# untitled.net
KiCad netlist of a schematic drawn in EAGLE
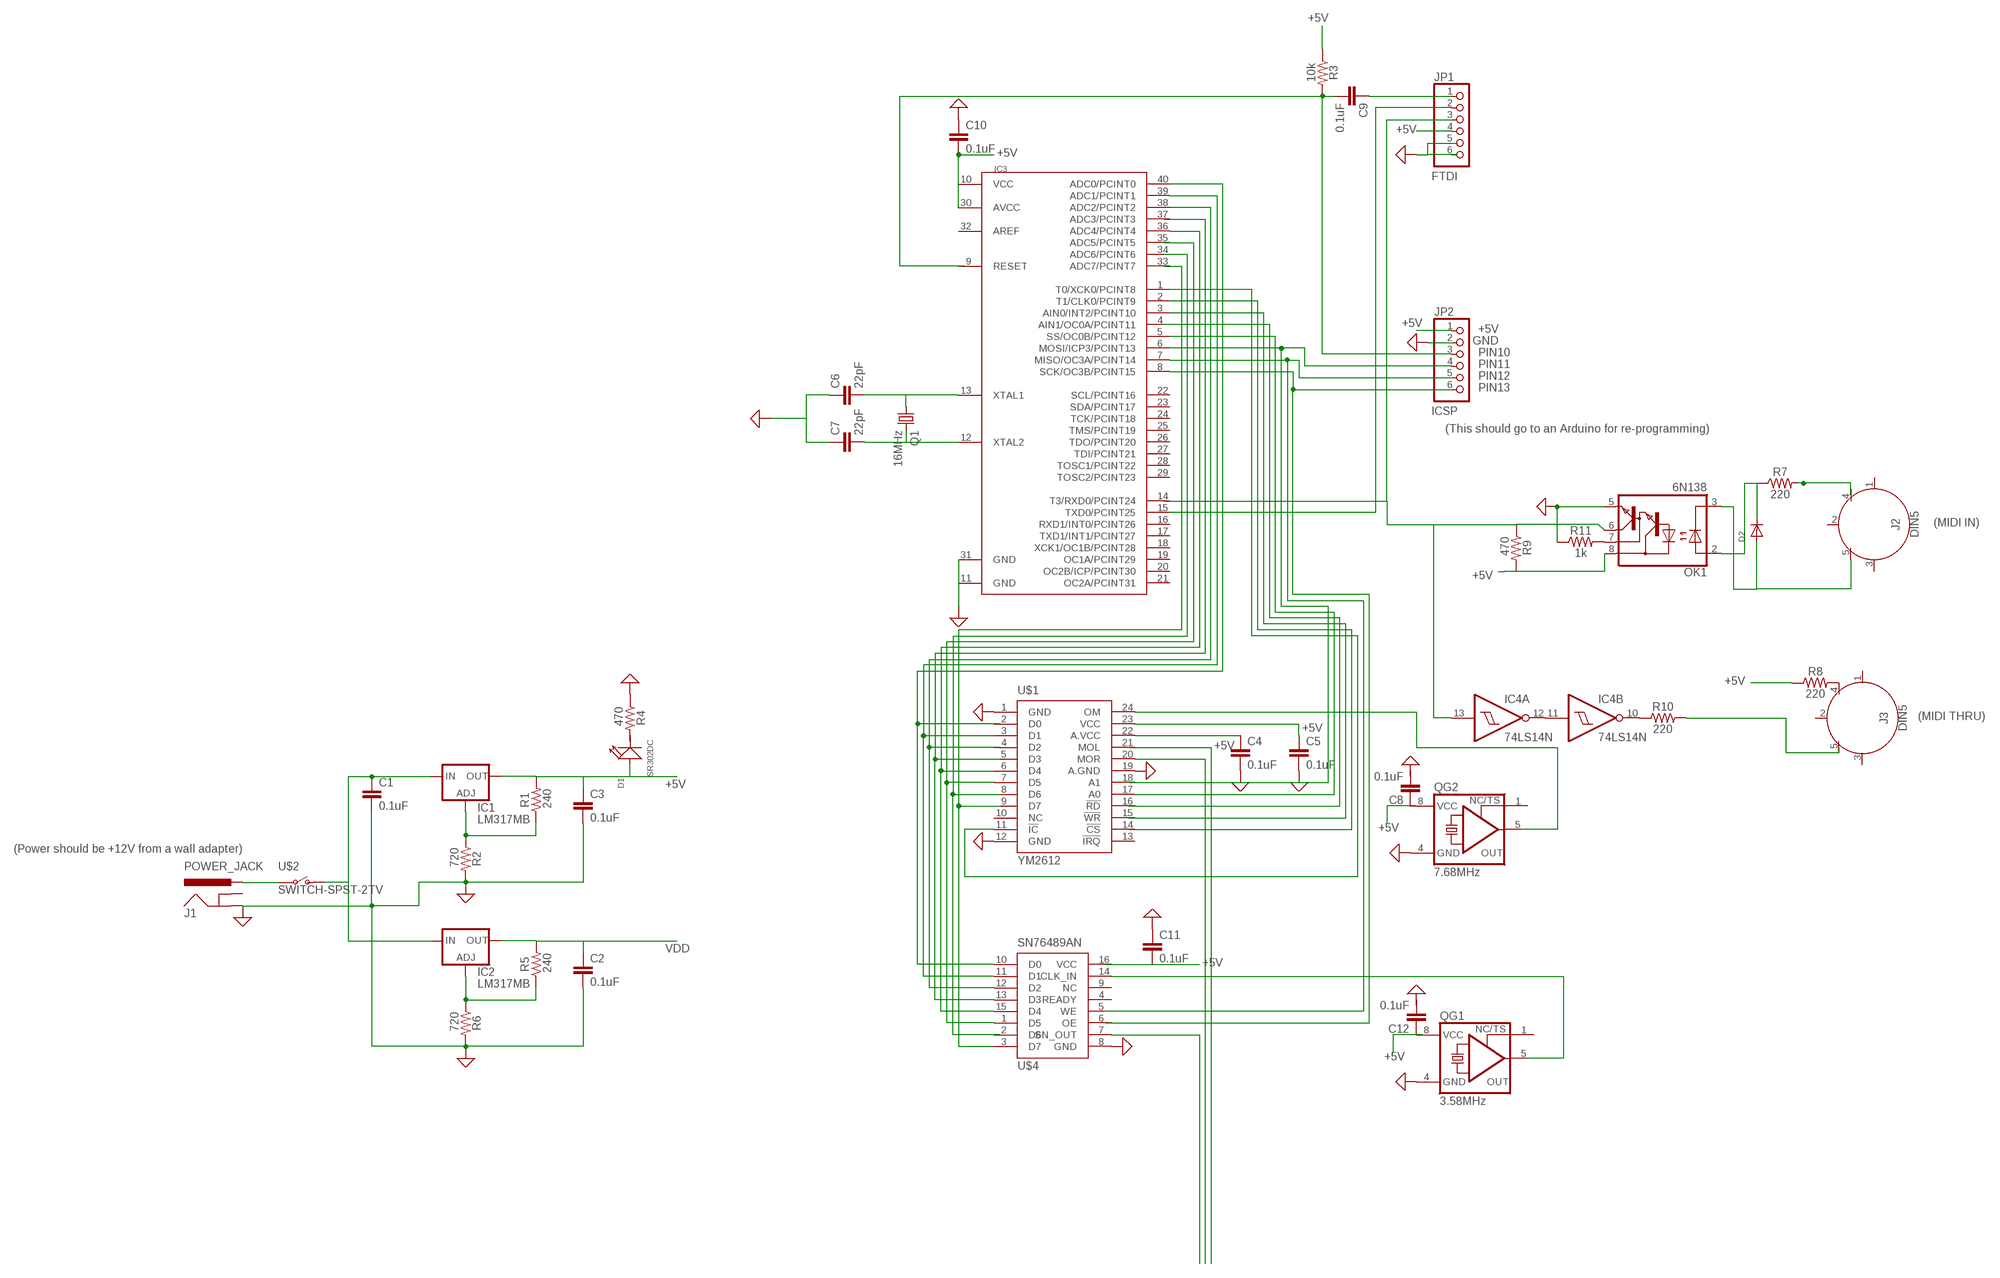
[diagram p0: schematic, sheet 1]

(export (version "E")
  (design (tool "Eeschema 10.0.6"))
  (components
    (comp (ref "C1")
      (value "0.1uF")
      (footprint "eagle-import:0402-CAP")
      (libsource (lib "eagle-import") (part ".1UF-CERCAP-08390"))
    )
    (comp (ref "C2")
      (value "0.1uF")
      (footprint "eagle-import:0402-CAP")
      (libsource (lib "eagle-import") (part ".1UF-CERCAP-08390"))
    )
    (comp (ref "C3")
      (value "0.1uF")
      (footprint "eagle-import:0402-CAP")
      (libsource (lib "eagle-import") (part ".1UF-CERCAP-08390"))
    )
    (comp (ref "C4")
      (value "0.1uF")
      (footprint "eagle-import:0402-CAP")
      (libsource (lib "eagle-import") (part ".1UF-CERCAP-08390"))
    )
    (comp (ref "C5")
      (value "0.1uF")
      (footprint "eagle-import:0402-CAP")
      (libsource (lib "eagle-import") (part ".1UF-CERCAP-08390"))
    )
    (comp (ref "C6")
      (value "22pF")
      (footprint "eagle-import:0402-CAP")
      (libsource (lib "eagle-import") (part ".1UF-CERCAP-08390"))
    )
    (comp (ref "C7")
      (value "22pF")
      (footprint "eagle-import:0402-CAP")
      (libsource (lib "eagle-import") (part ".1UF-CERCAP-08390"))
    )
    (comp (ref "C8")
      (value "0.1uF")
      (footprint "eagle-import:0402-CAP")
      (libsource (lib "eagle-import") (part ".1UF-CERCAP-08390"))
    )
    (comp (ref "C9")
      (value "0.1uF")
      (footprint "eagle-import:0402-CAP")
      (libsource (lib "eagle-import") (part ".1UF-CERCAP-08390"))
    )
    (comp (ref "C10")
      (value "0.1uF")
      (footprint "eagle-import:0402-CAP")
      (libsource (lib "eagle-import") (part ".1UF-CERCAP-08390"))
    )
    (comp (ref "C11")
      (value "0.1uF")
      (footprint "eagle-import:0402-CAP")
      (libsource (lib "eagle-import") (part ".1UF-CERCAP-08390"))
    )
    (comp (ref "C12")
      (value "0.1uF")
      (footprint "eagle-import:0402-CAP")
      (libsource (lib "eagle-import") (part ".1UF-CERCAP-08390"))
    )
    (comp (ref "D1")
      (value "SR302DC")
      (footprint "eagle-import:LED2-2.54-D3.0MM")
      (libsource (lib "eagle-import") (part "DIP-LED-RED-RED(2P-D3MM)"))
    )
    (comp (ref "D2")
      (value "DIODEDO-1N4148")
      (footprint "eagle-import:DO-1N4148")
      (libsource (lib "eagle-import") (part "DIODEDO-1N4148"))
    )
    (comp (ref "IC1")
      (value "LM317MB")
      (footprint "eagle-import:TO220L1")
      (libsource (lib "eagle-import") (part "LM317?MB"))
    )
    (comp (ref "IC2")
      (value "LM317MB")
      (footprint "eagle-import:TO220L1")
      (libsource (lib "eagle-import") (part "LM317?MB"))
    )
    (comp (ref "IC3")
      (value "MEGA1284P")
      (footprint "eagle-import:DIL40")
      (libsource (lib "eagle-import") (part "MEGA1284P"))
    )
    (comp (ref "IC4")
      (value "74LS14N")
      (footprint "eagle-import:DIL14")
      (libsource (lib "eagle-import") (part "7414NLS"))
    )
    (comp (ref "J1")
      (value "POWER_JACK")
      (footprint "eagle-import:POWER_JACK_PTH")
      (libsource (lib "eagle-import") (part "POWER_JACK"))
    )
    (comp (ref "J2")
      (value "DIN5")
      (footprint "eagle-import:DIN5-RA-PTH")
      (libsource (lib "eagle-import") (part "DIN5"))
    )
    (comp (ref "J3")
      (value "DIN5")
      (footprint "eagle-import:DIN5-RA-PTH")
      (libsource (lib "eagle-import") (part "DIN5"))
    )
    (comp (ref "JP1")
      (value "PINHD-1X6")
      (footprint "eagle-import:1X06")
      (libsource (lib "eagle-import") (part "PINHD-1X6"))
    )
    (comp (ref "JP2")
      (value "PINHD-1X6")
      (footprint "eagle-import:1X06")
      (libsource (lib "eagle-import") (part "PINHD-1X6"))
    )
    (comp (ref "OK1")
      (value "6N138")
      (footprint "eagle-import:DIL08")
      (fields (field (name "MF") "VISHAY/TELEFUNKEN"))
      (libsource (lib "eagle-import") (part "6N138"))
    )
    (comp (ref "Q1")
      (value "16MHz")
      (footprint "eagle-import:HC18U-H")
      (libsource (lib "eagle-import") (part "CRYSTALHC18U-H"))
    )
    (comp (ref "QG1")
      (value "3.58MHz")
      (footprint "eagle-import:DIL08S")
      (libsource (lib "eagle-import") (part "XO-8"))
    )
    (comp (ref "QG2")
      (value "7.68MHz")
      (footprint "eagle-import:DIL08S")
      (libsource (lib "eagle-import") (part "XO-8"))
    )
    (comp (ref "R1")
      (value "240")
      (footprint "eagle-import:AXIAL-0.3")
      (libsource (lib "eagle-import") (part "RESISTORAXIAL-0.3"))
    )
    (comp (ref "R2")
      (value "720")
      (footprint "eagle-import:AXIAL-0.3")
      (libsource (lib "eagle-import") (part "RESISTORAXIAL-0.3"))
    )
    (comp (ref "R3")
      (value "10k")
      (footprint "eagle-import:AXIAL-0.3")
      (libsource (lib "eagle-import") (part "RESISTORAXIAL-0.3"))
    )
    (comp (ref "R4")
      (value "470")
      (footprint "eagle-import:AXIAL-0.3")
      (libsource (lib "eagle-import") (part "RESISTORAXIAL-0.3"))
    )
    (comp (ref "R5")
      (value "240")
      (footprint "eagle-import:AXIAL-0.3")
      (libsource (lib "eagle-import") (part "RESISTORAXIAL-0.3"))
    )
    (comp (ref "R6")
      (value "720")
      (footprint "eagle-import:AXIAL-0.3")
      (libsource (lib "eagle-import") (part "RESISTORAXIAL-0.3"))
    )
    (comp (ref "R7")
      (value "220")
      (footprint "eagle-import:AXIAL-0.3")
      (libsource (lib "eagle-import") (part "RESISTORAXIAL-0.3"))
    )
    (comp (ref "R8")
      (value "220")
      (footprint "eagle-import:AXIAL-0.3")
      (libsource (lib "eagle-import") (part "RESISTORAXIAL-0.3"))
    )
    (comp (ref "R9")
      (value "470")
      (footprint "eagle-import:AXIAL-0.3")
      (libsource (lib "eagle-import") (part "RESISTORAXIAL-0.3"))
    )
    (comp (ref "R10")
      (value "220")
      (footprint "eagle-import:AXIAL-0.3")
      (libsource (lib "eagle-import") (part "RESISTORAXIAL-0.3"))
    )
    (comp (ref "R11")
      (value "1k")
      (footprint "eagle-import:AXIAL-0.3")
      (libsource (lib "eagle-import") (part "RESISTORAXIAL-0.3"))
    )
    (comp (ref "U$1")
      (value "YM2612")
      (footprint "eagle-import:DIP24")
      (libsource (lib "eagle-import") (part "YM2612"))
    )
    (comp (ref "U$2")
      (value "SWITCH-SPST-2TV")
      (footprint "eagle-import:SWITCH-SPST-VERTICAL")
      (libsource (lib "eagle-import") (part "SWITCH-SPST-2TV"))
    )
    (comp (ref "U$4")
      (value "SN76489AN")
      (footprint "eagle-import:DIP16")
      (libsource (lib "eagle-import") (part "SN76489AN"))
    )
  )
  (nets
    (net (code "1") (name "/+5V") (class "Default")
      (node (ref "C10") (pin "2") (pinfunction "2_2") (pintype "passive"))
      (node (ref "C11") (pin "2") (pinfunction "2_2") (pintype "passive"))
      (node (ref "C3") (pin "1") (pinfunction "1_1") (pintype "passive"))
      (node (ref "C4") (pin "1") (pinfunction "1_1") (pintype "passive"))
      (node (ref "C5") (pin "1") (pinfunction "1_1") (pintype "passive"))
      (node (ref "IC1") (pin "2") (pinfunction "OUT_2") (pintype "passive"))
      (node (ref "IC3") (pin "10") (pinfunction "VCC_10") (pintype "bidirectional"))
      (node (ref "IC3") (pin "30") (pinfunction "AVCC_30") (pintype "bidirectional"))
      (node (ref "JP1") (pin "4") (pinfunction "4_4") (pintype "passive"))
      (node (ref "JP2") (pin "1") (pinfunction "1_1") (pintype "passive"))
      (node (ref "OK1") (pin "8") (pinfunction "VCC_8") (pintype "passive"))
      (node (ref "R1") (pin "P$2") (pinfunction "2_P$2") (pintype "passive"))
      (node (ref "R3") (pin "P$1") (pinfunction "1_P$1") (pintype "passive"))
      (node (ref "R8") (pin "P$1") (pinfunction "1_P$1") (pintype "passive"))
      (node (ref "R9") (pin "P$2") (pinfunction "2_P$2") (pintype "passive"))
      (node (ref "U$1") (pin "22") (pinfunction "A.VCC_22") (pintype "bidirectional"))
      (node (ref "U$1") (pin "23") (pinfunction "VCC_23") (pintype "bidirectional"))
    )
    (net (code "2") (name "Net-(C9-Pad1)") (class "Default")
      (node (ref "C9") (pin "1") (pinfunction "1_1") (pintype "passive"))
      (node (ref "JP1") (pin "1") (pinfunction "1_1") (pintype "passive"))
    )
    (net (code "3") (name "Net-(IC1-ADJ)") (class "Default")
      (node (ref "IC1") (pin "1") (pinfunction "ADJ_1") (pintype "input"))
      (node (ref "R1") (pin "P$1") (pinfunction "1_P$1") (pintype "passive"))
      (node (ref "R2") (pin "P$1") (pinfunction "1_P$1") (pintype "passive"))
    )
    (net (code "4") (name "Net-(IC1-IN)") (class "Default")
      (node (ref "C1") (pin "1") (pinfunction "1_1") (pintype "passive"))
      (node (ref "IC1") (pin "3") (pinfunction "IN_3") (pintype "input"))
      (node (ref "IC2") (pin "3") (pinfunction "IN_3") (pintype "input"))
      (node (ref "U$2") (pin "1") (pinfunction "O_1") (pintype "passive"))
    )
    (net (code "5") (name "Net-(IC2-ADJ)") (class "Default")
      (node (ref "IC2") (pin "1") (pinfunction "ADJ_1") (pintype "input"))
      (node (ref "R5") (pin "P$1") (pinfunction "1_P$1") (pintype "passive"))
      (node (ref "R6") (pin "P$1") (pinfunction "1_P$1") (pintype "passive"))
    )
    (net (code "6") (name "Net-(IC2-OUT)") (class "Default")
      (node (ref "C2") (pin "1") (pinfunction "1_1") (pintype "passive"))
      (node (ref "IC2") (pin "2") (pinfunction "OUT_2") (pintype "passive"))
      (node (ref "R5") (pin "P$2") (pinfunction "2_P$2") (pintype "passive"))
    )
    (net (code "7") (name "Net-(IC3-ADC0{slash}PCINT0)") (class "Default")
      (node (ref "IC3") (pin "40") (pinfunction "ADC0/PCINT0_40") (pintype "bidirectional"))
      (node (ref "U$4") (pin "10") (pinfunction "D0_10") (pintype "bidirectional"))
    )
    (net (code "8") (name "Net-(IC3-ADC1{slash}PCINT1)") (class "Default")
      (node (ref "IC3") (pin "39") (pinfunction "ADC1/PCINT1_39") (pintype "bidirectional"))
      (node (ref "U$1") (pin "3") (pinfunction "D1_3") (pintype "bidirectional"))
      (node (ref "U$4") (pin "11") (pinfunction "D1_11") (pintype "bidirectional"))
    )
    (net (code "9") (name "Net-(IC3-ADC2{slash}PCINT2)") (class "Default")
      (node (ref "IC3") (pin "38") (pinfunction "ADC2/PCINT2_38") (pintype "bidirectional"))
      (node (ref "U$4") (pin "12") (pinfunction "D2_12") (pintype "bidirectional"))
    )
    (net (code "10") (name "Net-(IC3-ADC4{slash}PCINT4)") (class "Default")
      (node (ref "IC3") (pin "36") (pinfunction "ADC4/PCINT4_36") (pintype "bidirectional"))
      (node (ref "U$1") (pin "6") (pinfunction "D4_6") (pintype "bidirectional"))
      (node (ref "U$4") (pin "15") (pinfunction "D4_15") (pintype "bidirectional"))
    )
    (net (code "11") (name "Net-(IC3-MISO{slash}OC3A{slash}PCINT14)") (class "Default")
      (node (ref "IC3") (pin "7") (pinfunction "MISO/OC3A/PCINT14_7") (pintype "bidirectional"))
      (node (ref "JP2") (pin "5") (pinfunction "5_5") (pintype "passive"))
    )
    (net (code "12") (name "Net-(IC3-MOSI{slash}ICP3{slash}PCINT13)") (class "Default")
      (node (ref "IC3") (pin "6") (pinfunction "MOSI/ICP3/PCINT13_6") (pintype "bidirectional"))
      (node (ref "JP2") (pin "4") (pinfunction "4_4") (pintype "passive"))
    )
    (net (code "13") (name "Net-(IC3-SCK{slash}OC3B{slash}PCINT15)") (class "Default")
      (node (ref "IC3") (pin "8") (pinfunction "SCK/OC3B/PCINT15_8") (pintype "bidirectional"))
      (node (ref "JP2") (pin "6") (pinfunction "6_6") (pintype "passive"))
    )
    (net (code "14") (name "Net-(IC3-SS{slash}OC0B{slash}PCINT12)") (class "Default")
      (node (ref "IC3") (pin "5") (pinfunction "SS/OC0B/PCINT12_5") (pintype "bidirectional"))
      (node (ref "U$1") (pin "17") (pinfunction "A0_17") (pintype "bidirectional"))
    )
    (net (code "15") (name "Net-(IC3-T0{slash}XCK0{slash}PCINT8)") (class "Default")
      (node (ref "IC3") (pin "1") (pinfunction "T0/XCK0/PCINT8_1") (pintype "bidirectional"))
      (node (ref "U$1") (pin "11") (pinfunction "~{IC}_11") (pintype "bidirectional"))
    )
    (net (code "16") (name "Net-(IC3-TXD0{slash}PCINT25)") (class "Default")
      (node (ref "IC3") (pin "15") (pinfunction "TXD0/PCINT25_15") (pintype "bidirectional"))
      (node (ref "JP1") (pin "2") (pinfunction "2_2") (pintype "passive"))
    )
    (net (code "17") (name "Net-(IC3-XTAL1)") (class "Default")
      (node (ref "C6") (pin "2") (pinfunction "2_2") (pintype "passive"))
      (node (ref "IC3") (pin "13") (pinfunction "XTAL1_13") (pintype "bidirectional"))
      (node (ref "Q1") (pin "1") (pinfunction "1_1") (pintype "passive"))
    )
    (net (code "18") (name "Net-(IC3-XTAL2)") (class "Default")
      (node (ref "C7") (pin "2") (pinfunction "2_2") (pintype "passive"))
      (node (ref "IC3") (pin "12") (pinfunction "XTAL2_12") (pintype "bidirectional"))
      (node (ref "Q1") (pin "2") (pinfunction "2_2") (pintype "passive"))
    )
    (net (code "19") (name "Net-(IC4A-I)") (class "Default")
      (node (ref "IC4") (pin "13") (pinfunction "I_13") (pintype "input"))
      (node (ref "JP1") (pin "3") (pinfunction "3_3") (pintype "passive"))
      (node (ref "OK1") (pin "6") (pinfunction "VO_6") (pintype "passive"))
      (node (ref "R9") (pin "P$1") (pinfunction "1_P$1") (pintype "passive"))
    )
    (net (code "20") (name "Net-(IC4A-O)") (class "Default")
      (node (ref "IC4") (pin "11") (pinfunction "I_11") (pintype "input"))
      (node (ref "IC4") (pin "12") (pinfunction "O_12") (pintype "output"))
    )
    (net (code "21") (name "Net-(IC4B-O)") (class "Default")
      (node (ref "IC4") (pin "10") (pinfunction "O_10") (pintype "output"))
      (node (ref "R10") (pin "P$1") (pinfunction "1_P$1") (pintype "passive"))
    )
    (net (code "22") (name "Net-(OK1-A)") (class "Default")
      (node (ref "D2") (pin "C") (pinfunction "C_C") (pintype "passive"))
      (node (ref "OK1") (pin "2") (pinfunction "A_2") (pintype "passive"))
      (node (ref "R7") (pin "P$1") (pinfunction "1_P$1") (pintype "passive"))
    )
    (net (code "23") (name "Net-(OK1-C)") (class "Default")
      (node (ref "D2") (pin "A") (pinfunction "A_A") (pintype "passive"))
      (node (ref "J2") (pin "5") (pinfunction "5_5") (pintype "bidirectional"))
      (node (ref "OK1") (pin "3") (pinfunction "C_3") (pintype "passive"))
    )
    (net (code "24") (name "Net-(OK1-VB)") (class "Default")
      (node (ref "OK1") (pin "7") (pinfunction "VB_7") (pintype "passive"))
      (node (ref "R11") (pin "P$2") (pinfunction "2_P$2") (pintype "passive"))
    )
    (net (code "25") (name "Net-(QG1-VCC)") (class "Default")
      (node (ref "C12") (pin "1") (pinfunction "1_1") (pintype "passive"))
      (node (ref "QG1") (pin "8") (pinfunction "VCC_8") (pintype "power_in"))
    )
    (net (code "26") (name "Net-(QG2-VCC)") (class "Default")
      (node (ref "C8") (pin "1") (pinfunction "1_1") (pintype "passive"))
      (node (ref "QG2") (pin "8") (pinfunction "VCC_8") (pintype "power_in"))
    )
    (net (code "27") (name "Net-(R3-2)") (class "Default")
      (node (ref "C9") (pin "2") (pinfunction "2_2") (pintype "passive"))
      (node (ref "JP2") (pin "3") (pinfunction "3_3") (pintype "passive"))
      (node (ref "R3") (pin "P$2") (pinfunction "2_P$2") (pintype "passive"))
    )
    (net (code "28") (name "Net-(R8-2)") (class "Default")
      (node (ref "J3") (pin "4") (pinfunction "4_4") (pintype "bidirectional"))
      (node (ref "R8") (pin "P$2") (pinfunction "2_P$2") (pintype "passive"))
    )
    (net (code "29") (name "Net-(R10-2)") (class "Default")
      (node (ref "J3") (pin "5") (pinfunction "5_5") (pintype "bidirectional"))
      (node (ref "R10") (pin "P$2") (pinfunction "2_P$2") (pintype "passive"))
    )
    (net (code "30") (name "Net-(U$1-D5)") (class "Default")
      (node (ref "U$1") (pin "7") (pinfunction "D5_7") (pintype "bidirectional"))
      (node (ref "U$4") (pin "1") (pinfunction "D5_1") (pintype "bidirectional"))
    )
    (net (code "31") (name "Net-(U$2-P)") (class "Default")
      (node (ref "J1") (pin "PWR") (pinfunction "PWR_PWR") (pintype "bidirectional"))
      (node (ref "U$2") (pin "2") (pinfunction "P_2") (pintype "passive"))
    )
    (net (code "32") (name "SUP") (class "Default")
      (node (ref "C1") (pin "2") (pinfunction "2_2") (pintype "passive"))
      (node (ref "C10") (pin "1") (pinfunction "1_1") (pintype "passive"))
      (node (ref "C11") (pin "1") (pinfunction "1_1") (pintype "passive"))
      (node (ref "C2") (pin "2") (pinfunction "2_2") (pintype "passive"))
      (node (ref "C3") (pin "2") (pinfunction "2_2") (pintype "passive"))
      (node (ref "C4") (pin "2") (pinfunction "2_2") (pintype "passive"))
      (node (ref "C5") (pin "2") (pinfunction "2_2") (pintype "passive"))
      (node (ref "C6") (pin "1") (pinfunction "1_1") (pintype "passive"))
      (node (ref "C7") (pin "1") (pinfunction "1_1") (pintype "passive"))
      (node (ref "IC3") (pin "11") (pinfunction "GND_11") (pintype "bidirectional"))
      (node (ref "IC3") (pin "31") (pinfunction "GND_31") (pintype "bidirectional"))
      (node (ref "J1") (pin "GND") (pinfunction "GND_GND") (pintype "bidirectional"))
      (node (ref "JP2") (pin "2") (pinfunction "2_2") (pintype "passive"))
      (node (ref "OK1") (pin "5") (pinfunction "GND_5") (pintype "passive"))
      (node (ref "QG1") (pin "4") (pinfunction "GND_4") (pintype "power_in"))
      (node (ref "QG2") (pin "4") (pinfunction "GND_4") (pintype "power_in"))
      (node (ref "R11") (pin "P$1") (pinfunction "1_P$1") (pintype "passive"))
      (node (ref "R2") (pin "P$2") (pinfunction "2_P$2") (pintype "passive"))
      (node (ref "R4") (pin "P$1") (pinfunction "1_P$1") (pintype "passive"))
      (node (ref "R6") (pin "P$2") (pinfunction "2_P$2") (pintype "passive"))
      (node (ref "U$1") (pin "1") (pinfunction "GND_1") (pintype "bidirectional"))
      (node (ref "U$1") (pin "12") (pinfunction "GND_12") (pintype "bidirectional"))
      (node (ref "U$1") (pin "19") (pinfunction "A.GND_19") (pintype "bidirectional"))
      (node (ref "U$4") (pin "8") (pinfunction "GND_8") (pintype "bidirectional"))
    )
    (net (code "33") (name "unconnected-(C8-Pad2)") (class "Default")
      (node (ref "C8") (pin "2") (pinfunction "2_2") (pintype "passive"))
    )
    (net (code "34") (name "unconnected-(C12-Pad2)") (class "Default")
      (node (ref "C12") (pin "2") (pinfunction "2_2") (pintype "passive"))
    )
    (net (code "35") (name "unconnected-(D1-+-PadA)") (class "Default")
      (node (ref "D1") (pin "A") (pinfunction "+_A") (pintype "passive"))
    )
    (net (code "36") (name "unconnected-(D1---PadK)") (class "Default")
      (node (ref "D1") (pin "K") (pinfunction "-_K") (pintype "passive"))
    )
    (net (code "37") (name "unconnected-(IC3-ADC3{slash}PCINT3-Pad37)") (class "Default")
      (node (ref "IC3") (pin "37") (pinfunction "ADC3/PCINT3_37") (pintype "bidirectional"))
    )
    (net (code "38") (name "unconnected-(IC3-ADC5{slash}PCINT5-Pad35)") (class "Default")
      (node (ref "IC3") (pin "35") (pinfunction "ADC5/PCINT5_35") (pintype "bidirectional"))
    )
    (net (code "39") (name "unconnected-(IC3-ADC6{slash}PCINT6-Pad34)") (class "Default")
      (node (ref "IC3") (pin "34") (pinfunction "ADC6/PCINT6_34") (pintype "bidirectional"))
    )
    (net (code "40") (name "unconnected-(IC3-ADC7{slash}PCINT7-Pad33)") (class "Default")
      (node (ref "IC3") (pin "33") (pinfunction "ADC7/PCINT7_33") (pintype "bidirectional"))
    )
    (net (code "41") (name "unconnected-(IC3-AIN0{slash}INT2{slash}PCINT10-Pad3)") (class "Default")
      (node (ref "IC3") (pin "3") (pinfunction "AIN0/INT2/PCINT10_3") (pintype "bidirectional"))
    )
    (net (code "42") (name "unconnected-(IC3-AIN1{slash}OC0A{slash}PCINT11-Pad4)") (class "Default")
      (node (ref "IC3") (pin "4") (pinfunction "AIN1/OC0A/PCINT11_4") (pintype "bidirectional"))
    )
    (net (code "43") (name "unconnected-(IC3-AREF-Pad32)") (class "Default")
      (node (ref "IC3") (pin "32") (pinfunction "AREF_32") (pintype "bidirectional"))
    )
    (net (code "44") (name "unconnected-(IC3-OC1A{slash}PCINT29-Pad19)") (class "Default")
      (node (ref "IC3") (pin "19") (pinfunction "OC1A/PCINT29_19") (pintype "bidirectional"))
    )
    (net (code "45") (name "unconnected-(IC3-OC2A{slash}PCINT31-Pad21)") (class "Default")
      (node (ref "IC3") (pin "21") (pinfunction "OC2A/PCINT31_21") (pintype "bidirectional"))
    )
    (net (code "46") (name "unconnected-(IC3-OC2B{slash}ICP{slash}PCINT30-Pad20)") (class "Default")
      (node (ref "IC3") (pin "20") (pinfunction "OC2B/ICP/PCINT30_20") (pintype "bidirectional"))
    )
    (net (code "47") (name "unconnected-(IC3-RESET-Pad9)") (class "Default")
      (node (ref "IC3") (pin "9") (pinfunction "RESET_9") (pintype "bidirectional"))
    )
    (net (code "48") (name "unconnected-(IC3-RXD1{slash}INT0{slash}PCINT26-Pad16)") (class "Default")
      (node (ref "IC3") (pin "16") (pinfunction "RXD1/INT0/PCINT26_16") (pintype "bidirectional"))
    )
    (net (code "49") (name "unconnected-(IC3-SCL{slash}PCINT16-Pad22)") (class "Default")
      (node (ref "IC3") (pin "22") (pinfunction "SCL/PCINT16_22") (pintype "bidirectional"))
    )
    (net (code "50") (name "unconnected-(IC3-SDA{slash}PCINT17-Pad23)") (class "Default")
      (node (ref "IC3") (pin "23") (pinfunction "SDA/PCINT17_23") (pintype "bidirectional"))
    )
    (net (code "51") (name "unconnected-(IC3-T1{slash}CLK0{slash}PCINT9-Pad2)") (class "Default")
      (node (ref "IC3") (pin "2") (pinfunction "T1/CLK0/PCINT9_2") (pintype "bidirectional"))
    )
    (net (code "52") (name "unconnected-(IC3-T3{slash}RXD0{slash}PCINT24-Pad14)") (class "Default")
      (node (ref "IC3") (pin "14") (pinfunction "T3/RXD0/PCINT24_14") (pintype "bidirectional"))
    )
    (net (code "53") (name "unconnected-(IC3-TCK{slash}PCINT18-Pad24)") (class "Default")
      (node (ref "IC3") (pin "24") (pinfunction "TCK/PCINT18_24") (pintype "bidirectional"))
    )
    (net (code "54") (name "unconnected-(IC3-TDI{slash}PCINT21-Pad27)") (class "Default")
      (node (ref "IC3") (pin "27") (pinfunction "TDI/PCINT21_27") (pintype "bidirectional"))
    )
    (net (code "55") (name "unconnected-(IC3-TDO{slash}PCINT20-Pad26)") (class "Default")
      (node (ref "IC3") (pin "26") (pinfunction "TDO/PCINT20_26") (pintype "bidirectional"))
    )
    (net (code "56") (name "unconnected-(IC3-TMS{slash}PCINT19-Pad25)") (class "Default")
      (node (ref "IC3") (pin "25") (pinfunction "TMS/PCINT19_25") (pintype "bidirectional"))
    )
    (net (code "57") (name "unconnected-(IC3-TOSC1{slash}PCINT22-Pad28)") (class "Default")
      (node (ref "IC3") (pin "28") (pinfunction "TOSC1/PCINT22_28") (pintype "bidirectional"))
    )
    (net (code "58") (name "unconnected-(IC3-TOSC2{slash}PCINT23-Pad29)") (class "Default")
      (node (ref "IC3") (pin "29") (pinfunction "TOSC2/PCINT23_29") (pintype "bidirectional"))
    )
    (net (code "59") (name "unconnected-(IC3-TXD1{slash}INT1{slash}PCINT27-Pad17)") (class "Default")
      (node (ref "IC3") (pin "17") (pinfunction "TXD1/INT1/PCINT27_17") (pintype "bidirectional"))
    )
    (net (code "60") (name "unconnected-(IC3-XCK1{slash}OC1B{slash}PCINT28-Pad18)") (class "Default")
      (node (ref "IC3") (pin "18") (pinfunction "XCK1/OC1B/PCINT28_18") (pintype "bidirectional"))
    )
    (net (code "61") (name "unconnected-(J1-PadGNDBREAK)") (class "Default")
      (node (ref "J1") (pin "GNDBREAK") (pinfunction "GNDBREAK_GNDBREAK") (pintype "bidirectional"))
    )
    (net (code "62") (name "unconnected-(J2-Pad1)") (class "Default")
      (node (ref "J2") (pin "1") (pinfunction "1_1") (pintype "bidirectional"))
    )
    (net (code "63") (name "unconnected-(J2-Pad2)") (class "Default")
      (node (ref "J2") (pin "2") (pinfunction "2_2") (pintype "bidirectional"))
    )
    (net (code "64") (name "unconnected-(J2-Pad3)") (class "Default")
      (node (ref "J2") (pin "3") (pinfunction "3_3") (pintype "bidirectional"))
    )
    (net (code "65") (name "unconnected-(J2-Pad4)") (class "Default")
      (node (ref "J2") (pin "4") (pinfunction "4_4") (pintype "bidirectional"))
    )
    (net (code "66") (name "unconnected-(J3-Pad1)") (class "Default")
      (node (ref "J3") (pin "1") (pinfunction "1_1") (pintype "bidirectional"))
    )
    (net (code "67") (name "unconnected-(J3-Pad2)") (class "Default")
      (node (ref "J3") (pin "2") (pinfunction "2_2") (pintype "bidirectional"))
    )
    (net (code "68") (name "unconnected-(J3-Pad3)") (class "Default")
      (node (ref "J3") (pin "3") (pinfunction "3_3") (pintype "bidirectional"))
    )
    (net (code "69") (name "unconnected-(JP1-Pad5)") (class "Default")
      (node (ref "JP1") (pin "5") (pinfunction "5_5") (pintype "passive"))
    )
    (net (code "70") (name "unconnected-(JP1-Pad6)") (class "Default")
      (node (ref "JP1") (pin "6") (pinfunction "6_6") (pintype "passive"))
    )
    (net (code "71") (name "unconnected-(QG1-OUT-Pad5)") (class "Default")
      (node (ref "QG1") (pin "5") (pinfunction "OUT_5") (pintype "output"))
    )
    (net (code "72") (name "unconnected-(QG1-TS-Pad1)") (class "Default")
      (node (ref "QG1") (pin "1") (pinfunction "TS_1") (pintype "passive"))
    )
    (net (code "73") (name "unconnected-(QG2-OUT-Pad5)") (class "Default")
      (node (ref "QG2") (pin "5") (pinfunction "OUT_5") (pintype "output"))
    )
    (net (code "74") (name "unconnected-(QG2-TS-Pad1)") (class "Default")
      (node (ref "QG2") (pin "1") (pinfunction "TS_1") (pintype "passive"))
    )
    (net (code "75") (name "unconnected-(R4-2-PadP$2)") (class "Default")
      (node (ref "R4") (pin "P$2") (pinfunction "2_P$2") (pintype "passive"))
    )
    (net (code "76") (name "unconnected-(R7-2-PadP$2)") (class "Default")
      (node (ref "R7") (pin "P$2") (pinfunction "2_P$2") (pintype "passive"))
    )
    (net (code "77") (name "unconnected-(U$1-A1-Pad18)") (class "Default")
      (node (ref "U$1") (pin "18") (pinfunction "A1_18") (pintype "bidirectional"))
    )
    (net (code "78") (name "unconnected-(U$1-D0-Pad2)") (class "Default")
      (node (ref "U$1") (pin "2") (pinfunction "D0_2") (pintype "bidirectional"))
    )
    (net (code "79") (name "unconnected-(U$1-D2-Pad4)") (class "Default")
      (node (ref "U$1") (pin "4") (pinfunction "D2_4") (pintype "bidirectional"))
    )
    (net (code "80") (name "unconnected-(U$1-D3-Pad5)") (class "Default")
      (node (ref "U$1") (pin "5") (pinfunction "D3_5") (pintype "bidirectional"))
    )
    (net (code "81") (name "unconnected-(U$1-D6-Pad8)") (class "Default")
      (node (ref "U$1") (pin "8") (pinfunction "D6_8") (pintype "bidirectional"))
    )
    (net (code "82") (name "unconnected-(U$1-D7-Pad9)") (class "Default")
      (node (ref "U$1") (pin "9") (pinfunction "D7_9") (pintype "bidirectional"))
    )
    (net (code "83") (name "unconnected-(U$1-MOL-Pad21)") (class "Default")
      (node (ref "U$1") (pin "21") (pinfunction "MOL_21") (pintype "bidirectional"))
    )
    (net (code "84") (name "unconnected-(U$1-MOR-Pad20)") (class "Default")
      (node (ref "U$1") (pin "20") (pinfunction "MOR_20") (pintype "bidirectional"))
    )
    (net (code "85") (name "unconnected-(U$1-NC-Pad10)") (class "Default")
      (node (ref "U$1") (pin "10") (pinfunction "NC_10") (pintype "bidirectional"))
    )
    (net (code "86") (name "unconnected-(U$1-OM-Pad24)") (class "Default")
      (node (ref "U$1") (pin "24") (pinfunction "OM_24") (pintype "bidirectional"))
    )
    (net (code "87") (name "unconnected-(U$1-~{CS}-Pad14)") (class "Default")
      (node (ref "U$1") (pin "14") (pinfunction "~{CS}_14") (pintype "bidirectional"))
    )
    (net (code "88") (name "unconnected-(U$1-~{IRQ}-Pad13)") (class "Default")
      (node (ref "U$1") (pin "13") (pinfunction "~{IRQ}_13") (pintype "bidirectional"))
    )
    (net (code "89") (name "unconnected-(U$1-~{RD}-Pad16)") (class "Default")
      (node (ref "U$1") (pin "16") (pinfunction "~{RD}_16") (pintype "bidirectional"))
    )
    (net (code "90") (name "unconnected-(U$1-~{WR}-Pad15)") (class "Default")
      (node (ref "U$1") (pin "15") (pinfunction "~{WR}_15") (pintype "bidirectional"))
    )
    (net (code "91") (name "unconnected-(U$4-CLK_IN-Pad14)") (class "Default")
      (node (ref "U$4") (pin "14") (pinfunction "CLK_IN_14") (pintype "bidirectional"))
    )
    (net (code "92") (name "unconnected-(U$4-D3-Pad13)") (class "Default")
      (node (ref "U$4") (pin "13") (pinfunction "D3_13") (pintype "bidirectional"))
    )
    (net (code "93") (name "unconnected-(U$4-D6-Pad2)") (class "Default")
      (node (ref "U$4") (pin "2") (pinfunction "D6_2") (pintype "bidirectional"))
    )
    (net (code "94") (name "unconnected-(U$4-D7-Pad3)") (class "Default")
      (node (ref "U$4") (pin "3") (pinfunction "D7_3") (pintype "bidirectional"))
    )
    (net (code "95") (name "unconnected-(U$4-NC-Pad9)") (class "Default")
      (node (ref "U$4") (pin "9") (pinfunction "NC_9") (pintype "bidirectional"))
    )
    (net (code "96") (name "unconnected-(U$4-OE-Pad6)") (class "Default")
      (node (ref "U$4") (pin "6") (pinfunction "OE_6") (pintype "bidirectional"))
    )
    (net (code "97") (name "unconnected-(U$4-READY-Pad4)") (class "Default")
      (node (ref "U$4") (pin "4") (pinfunction "READY_4") (pintype "bidirectional"))
    )
    (net (code "98") (name "unconnected-(U$4-SN_OUT-Pad7)") (class "Default")
      (node (ref "U$4") (pin "7") (pinfunction "SN_OUT_7") (pintype "bidirectional"))
    )
    (net (code "99") (name "unconnected-(U$4-VCC-Pad16)") (class "Default")
      (node (ref "U$4") (pin "16") (pinfunction "VCC_16") (pintype "bidirectional"))
    )
    (net (code "100") (name "unconnected-(U$4-WE-Pad5)") (class "Default")
      (node (ref "U$4") (pin "5") (pinfunction "WE_5") (pintype "bidirectional"))
    )
  )
)
